# PCM5102a_FG_Small_1.net
KiCad netlist of a schematic drawn in EAGLE
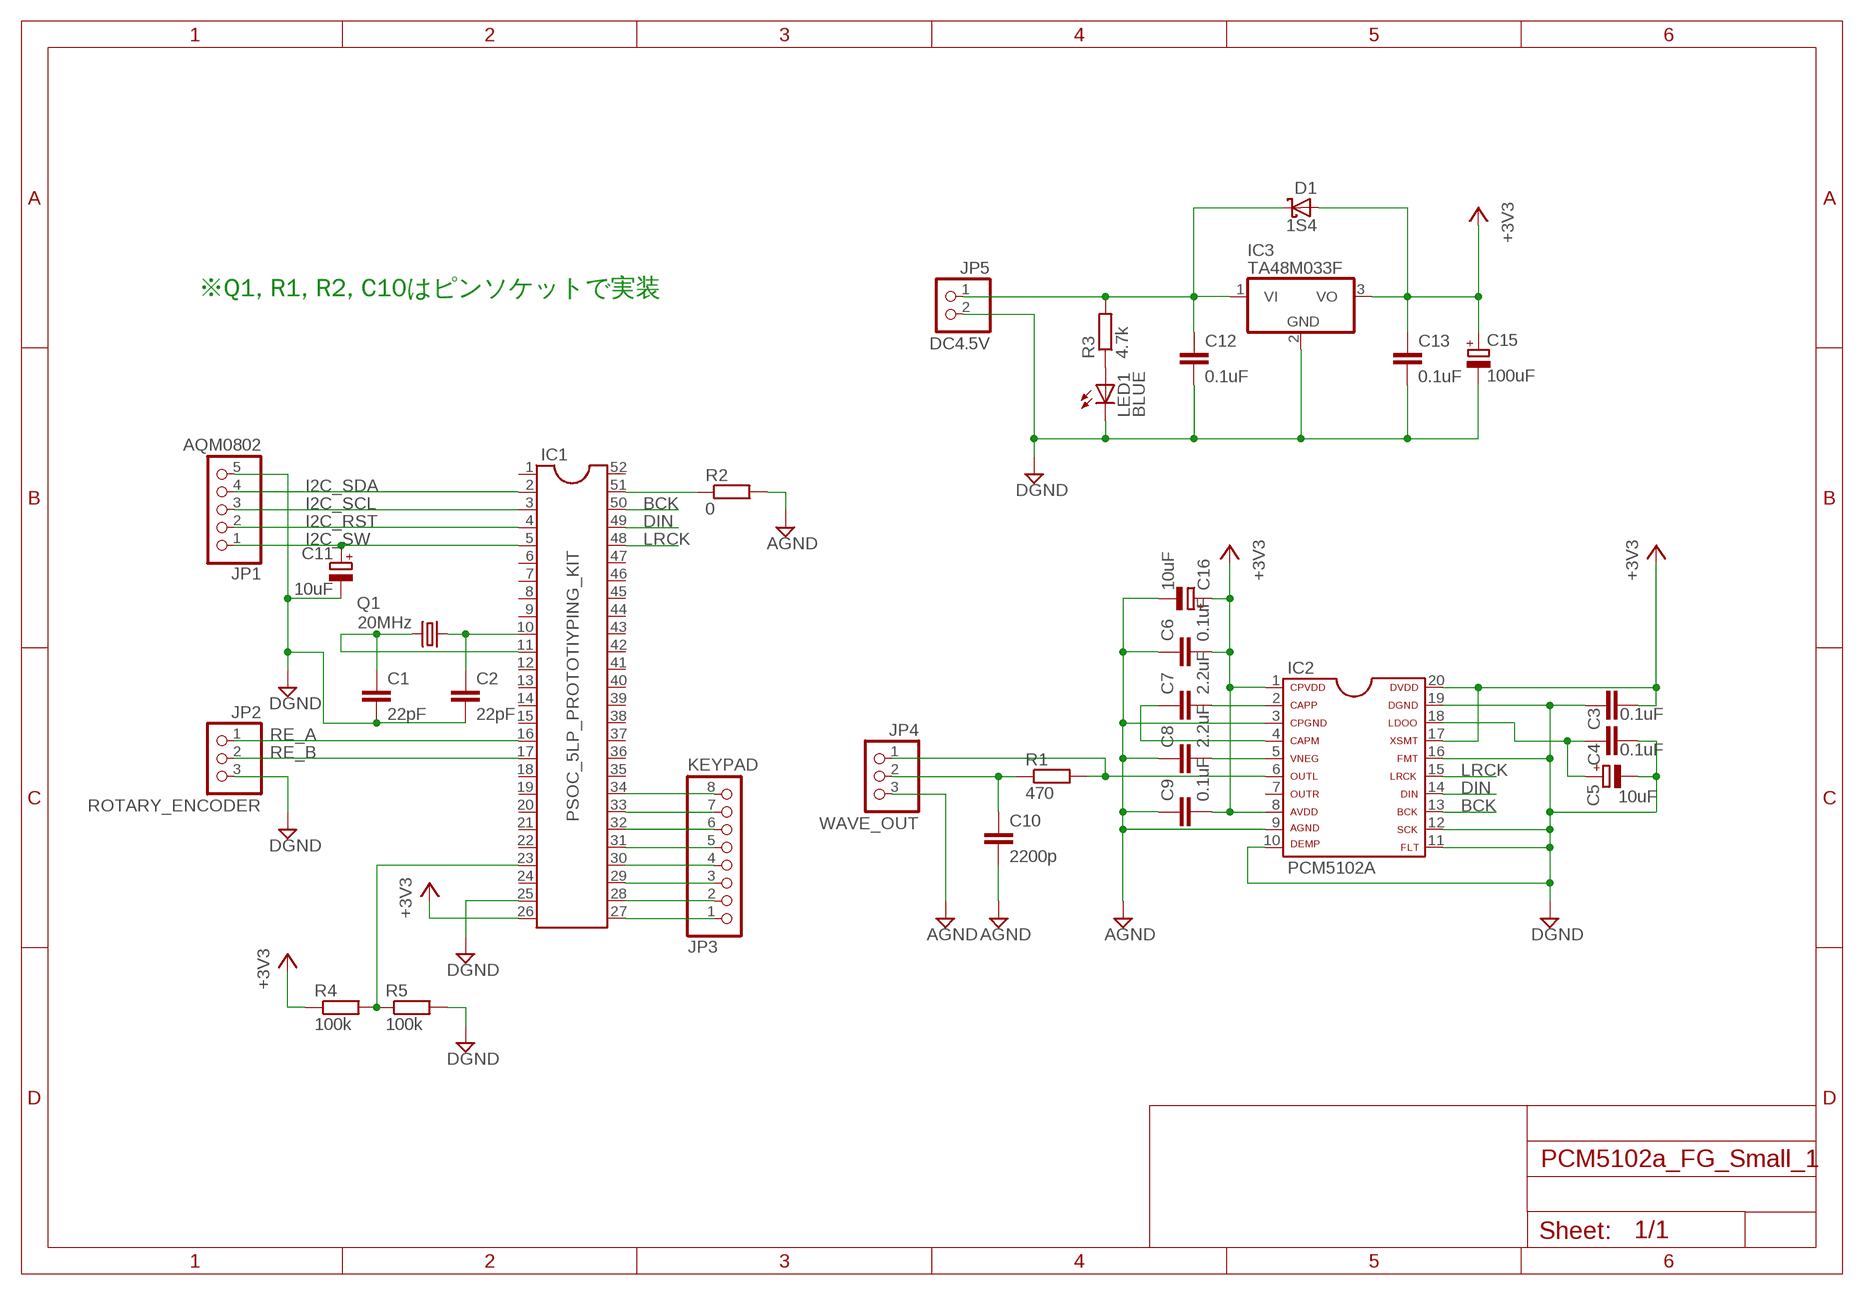
[diagram p0: schematic, sheet 1]

(export (version "E")
  (design (tool "Eeschema 10.0.6"))
  (components
    (comp (ref "C1")
      (value "22pF")
      (footprint "eagle-import:C050-024X044")
      (libsource (lib "eagle-import") (part "C-EU050-024X044"))
    )
    (comp (ref "C2")
      (value "22pF")
      (footprint "eagle-import:C050-024X044")
      (libsource (lib "eagle-import") (part "C-EU050-024X044"))
    )
    (comp (ref "C3")
      (value "0.1uF")
      (footprint "eagle-import:C025-024X044")
      (libsource (lib "eagle-import") (part "C-EU025-024X044"))
    )
    (comp (ref "C4")
      (value "0.1uF")
      (footprint "eagle-import:C025-024X044")
      (libsource (lib "eagle-import") (part "C-EU025-024X044"))
    )
    (comp (ref "C5")
      (value "10uF")
      (footprint "eagle-import:E2,5-5")
      (libsource (lib "eagle-import") (part "CPOL-EUE2.5-5"))
    )
    (comp (ref "C6")
      (value "0.1uF")
      (footprint "eagle-import:C025-024X044")
      (libsource (lib "eagle-import") (part "C-EU025-024X044"))
    )
    (comp (ref "C7")
      (value "2.2uF")
      (footprint "eagle-import:C075-063X106")
      (libsource (lib "eagle-import") (part "C-EU075-063X106"))
    )
    (comp (ref "C8")
      (value "2.2uF")
      (footprint "eagle-import:C075-063X106")
      (libsource (lib "eagle-import") (part "C-EU075-063X106"))
    )
    (comp (ref "C9")
      (value "0.1uF")
      (footprint "eagle-import:C025-024X044")
      (libsource (lib "eagle-import") (part "C-EU025-024X044"))
    )
    (comp (ref "C10")
      (value "2200p")
      (footprint "eagle-import:C050-035X075")
      (libsource (lib "eagle-import") (part "C-EU050-035X075"))
    )
    (comp (ref "C11")
      (value "10uF")
      (footprint "eagle-import:E2,5-5")
      (libsource (lib "eagle-import") (part "CPOL-EUE2.5-5"))
    )
    (comp (ref "C12")
      (value "0.1uF")
      (footprint "eagle-import:C025-024X044")
      (libsource (lib "eagle-import") (part "C-EU025-024X044"))
    )
    (comp (ref "C13")
      (value "0.1uF")
      (footprint "eagle-import:C025-024X044")
      (libsource (lib "eagle-import") (part "C-EU025-024X044"))
    )
    (comp (ref "C15")
      (value "100uF")
      (footprint "eagle-import:E2,5-7")
      (libsource (lib "eagle-import") (part "CPOL-EUE2.5-7"))
    )
    (comp (ref "C16")
      (value "10uF")
      (footprint "eagle-import:E2,5-5")
      (libsource (lib "eagle-import") (part "CPOL-EUE2.5-5"))
    )
    (comp (ref "D1")
      (value "1S4")
      (footprint "eagle-import:DO35-7")
      (libsource (lib "eagle-import") (part "SCHOTTKY-DIODEDO35-7"))
    )
    (comp (ref "IC1")
      (value "PSOC_5LP_PROTOTIYPING_KIT")
      (footprint "eagle-import:DIL52-8")
      (libsource (lib "eagle-import") (part "PSOC_5LP_PROTOTIYPING_KIT"))
    )
    (comp (ref "IC2")
      (value "PCM5102A")
      (footprint "eagle-import:DIL20-6")
      (libsource (lib "eagle-import") (part "PCM5102A"))
    )
    (comp (ref "IC3")
      (value "TA48M033F")
      (footprint "eagle-import:TO220V")
      (libsource (lib "eagle-import") (part "78TV05"))
    )
    (comp (ref "JP1")
      (value "AQM0802")
      (footprint "eagle-import:1X05")
      (libsource (lib "eagle-import") (part "PINHD-1X5"))
    )
    (comp (ref "JP2")
      (value "ROTARY_ENCODER")
      (footprint "eagle-import:1X03")
      (libsource (lib "eagle-import") (part "PINHD-1X3"))
    )
    (comp (ref "JP3")
      (value "KEYPAD")
      (footprint "eagle-import:1X08")
      (libsource (lib "eagle-import") (part "PINHD-1X8"))
    )
    (comp (ref "JP4")
      (value "WAVE_OUT")
      (footprint "eagle-import:1X03")
      (libsource (lib "eagle-import") (part "PINHD-1X3"))
    )
    (comp (ref "JP5")
      (value "DC4.5V")
      (footprint "eagle-import:1X02")
      (libsource (lib "eagle-import") (part "PINHD-1X2"))
    )
    (comp (ref "LED1")
      (value "BLUE")
      (footprint "eagle-import:LED3MM")
      (libsource (lib "eagle-import") (part "LED3MM"))
    )
    (comp (ref "Q1")
      (value "20MHz")
      (footprint "eagle-import:HC49_S")
      (libsource (lib "eagle-import") (part "CRYSTALHC49S"))
    )
    (comp (ref "R1")
      (value "470")
      (footprint "eagle-import:0207_7")
      (libsource (lib "eagle-import") (part "R-EU_0207/7"))
    )
    (comp (ref "R2")
      (value "0")
      (footprint "eagle-import:0207_7")
      (libsource (lib "eagle-import") (part "resistor_R-EU_0207/7"))
    )
    (comp (ref "R3")
      (value "4.7k")
      (footprint "eagle-import:0207_7")
      (libsource (lib "eagle-import") (part "resistor_R-EU_0207/7"))
    )
    (comp (ref "R4")
      (value "100k")
      (footprint "eagle-import:0207_7")
      (libsource (lib "eagle-import") (part "resistor_R-EU_0207/7"))
    )
    (comp (ref "R5")
      (value "100k")
      (footprint "eagle-import:0207_7")
      (libsource (lib "eagle-import") (part "resistor_R-EU_0207/7"))
    )
  )
  (nets
    (net (code "1") (name "+3V3") (class "Default")
      (node (ref "C13") (pin "1") (pinfunction "1_1") (pintype "passive"))
      (node (ref "C15") (pin "+") (pinfunction "+_+") (pintype "passive"))
      (node (ref "C16") (pin "+") (pinfunction "+_+") (pintype "passive"))
      (node (ref "C3") (pin "2") (pinfunction "2_2") (pintype "passive"))
      (node (ref "C6") (pin "2") (pinfunction "2_2") (pintype "passive"))
      (node (ref "C9") (pin "2") (pinfunction "2_2") (pintype "passive"))
      (node (ref "D1") (pin "A") (pinfunction "A_A") (pintype "passive"))
      (node (ref "IC1") (pin "26") (pinfunction "26_26") (pintype "passive"))
      (node (ref "IC2") (pin "1") (pinfunction "1_1") (pintype "passive"))
      (node (ref "IC2") (pin "17") (pinfunction "17_17") (pintype "passive"))
      (node (ref "IC2") (pin "20") (pinfunction "20_20") (pintype "passive"))
      (node (ref "IC2") (pin "8") (pinfunction "8_8") (pintype "passive"))
      (node (ref "IC3") (pin "3") (pinfunction "VO_3") (pintype "passive"))
      (node (ref "R4") (pin "1") (pinfunction "1_1") (pintype "passive"))
    )
    (net (code "2") (name "/BCK") (class "Default")
      (node (ref "IC1") (pin "50") (pinfunction "50_50") (pintype "passive"))
      (node (ref "IC2") (pin "13") (pinfunction "13_13") (pintype "passive"))
    )
    (net (code "3") (name "/DIN") (class "Default")
      (node (ref "IC1") (pin "49") (pinfunction "49_49") (pintype "passive"))
      (node (ref "IC2") (pin "14") (pinfunction "14_14") (pintype "passive"))
    )
    (net (code "4") (name "/I2C_RST") (class "Default")
      (node (ref "IC1") (pin "4") (pinfunction "4_4") (pintype "passive"))
      (node (ref "JP1") (pin "2") (pinfunction "2_2") (pintype "passive"))
    )
    (net (code "5") (name "/I2C_SCL") (class "Default")
      (node (ref "IC1") (pin "3") (pinfunction "3_3") (pintype "passive"))
      (node (ref "JP1") (pin "3") (pinfunction "3_3") (pintype "passive"))
    )
    (net (code "6") (name "/I2C_SDA") (class "Default")
      (node (ref "IC1") (pin "2") (pinfunction "2_2") (pintype "passive"))
      (node (ref "JP1") (pin "4") (pinfunction "4_4") (pintype "passive"))
    )
    (net (code "7") (name "/I2C_SW") (class "Default")
      (node (ref "C11") (pin "+") (pinfunction "+_+") (pintype "passive"))
      (node (ref "IC1") (pin "5") (pinfunction "5_5") (pintype "passive"))
      (node (ref "JP1") (pin "1") (pinfunction "1_1") (pintype "passive"))
    )
    (net (code "8") (name "/LRCK") (class "Default")
      (node (ref "IC1") (pin "48") (pinfunction "48_48") (pintype "passive"))
      (node (ref "IC2") (pin "15") (pinfunction "15_15") (pintype "passive"))
    )
    (net (code "9") (name "/RE_A") (class "Default")
      (node (ref "IC1") (pin "16") (pinfunction "16_16") (pintype "passive"))
      (node (ref "JP2") (pin "1") (pinfunction "1_1") (pintype "passive"))
    )
    (net (code "10") (name "/RE_B") (class "Default")
      (node (ref "IC1") (pin "17") (pinfunction "17_17") (pintype "passive"))
      (node (ref "JP2") (pin "2") (pinfunction "2_2") (pintype "passive"))
    )
    (net (code "11") (name "AGND") (class "Default")
      (node (ref "C10") (pin "2") (pinfunction "2_2") (pintype "passive"))
      (node (ref "C16") (pin "-") (pinfunction "-_-") (pintype "passive"))
      (node (ref "C6") (pin "1") (pinfunction "1_1") (pintype "passive"))
      (node (ref "C8") (pin "1") (pinfunction "1_1") (pintype "passive"))
      (node (ref "C9") (pin "1") (pinfunction "1_1") (pintype "passive"))
      (node (ref "IC2") (pin "3") (pinfunction "3_3") (pintype "passive"))
      (node (ref "IC2") (pin "9") (pinfunction "9_9") (pintype "passive"))
      (node (ref "JP4") (pin "3") (pinfunction "3_3") (pintype "passive"))
      (node (ref "R2") (pin "2") (pinfunction "2_2") (pintype "passive"))
    )
    (net (code "12") (name "DGND") (class "Default")
      (node (ref "C1") (pin "2") (pinfunction "2_2") (pintype "passive"))
      (node (ref "C11") (pin "-") (pinfunction "-_-") (pintype "passive"))
      (node (ref "C12") (pin "2") (pinfunction "2_2") (pintype "passive"))
      (node (ref "C13") (pin "2") (pinfunction "2_2") (pintype "passive"))
      (node (ref "C15") (pin "-") (pinfunction "-_-") (pintype "passive"))
      (node (ref "C2") (pin "2") (pinfunction "2_2") (pintype "passive"))
      (node (ref "C3") (pin "1") (pinfunction "1_1") (pintype "passive"))
      (node (ref "C4") (pin "2") (pinfunction "2_2") (pintype "passive"))
      (node (ref "C5") (pin "-") (pinfunction "-_-") (pintype "passive"))
      (node (ref "IC1") (pin "25") (pinfunction "25_25") (pintype "passive"))
      (node (ref "IC2") (pin "10") (pinfunction "10_10") (pintype "passive"))
      (node (ref "IC2") (pin "11") (pinfunction "11_11") (pintype "passive"))
      (node (ref "IC2") (pin "12") (pinfunction "12_12") (pintype "passive"))
      (node (ref "IC2") (pin "16") (pinfunction "16_16") (pintype "passive"))
      (node (ref "IC2") (pin "19") (pinfunction "19_19") (pintype "passive"))
      (node (ref "IC3") (pin "2") (pinfunction "GND_2") (pintype "passive"))
      (node (ref "JP1") (pin "5") (pinfunction "5_5") (pintype "passive"))
      (node (ref "JP2") (pin "3") (pinfunction "3_3") (pintype "passive"))
      (node (ref "JP5") (pin "2") (pinfunction "2_2") (pintype "passive"))
      (node (ref "LED1") (pin "K") (pinfunction "C_K") (pintype "passive"))
      (node (ref "R5") (pin "2") (pinfunction "2_2") (pintype "passive"))
    )
    (net (code "13") (name "Net-(C1-Pad1)") (class "Default")
      (node (ref "C1") (pin "1") (pinfunction "1_1") (pintype "passive"))
      (node (ref "IC1") (pin "11") (pinfunction "11_11") (pintype "passive"))
      (node (ref "Q1") (pin "2") (pinfunction "2_2") (pintype "passive"))
    )
    (net (code "14") (name "Net-(C2-Pad1)") (class "Default")
      (node (ref "C2") (pin "1") (pinfunction "1_1") (pintype "passive"))
      (node (ref "IC1") (pin "10") (pinfunction "10_10") (pintype "passive"))
      (node (ref "Q1") (pin "1") (pinfunction "1_1") (pintype "passive"))
    )
    (net (code "15") (name "Net-(C4-Pad1)") (class "Default")
      (node (ref "C4") (pin "1") (pinfunction "1_1") (pintype "passive"))
      (node (ref "C5") (pin "+") (pinfunction "+_+") (pintype "passive"))
      (node (ref "IC2") (pin "18") (pinfunction "18_18") (pintype "passive"))
    )
    (net (code "16") (name "Net-(C7-Pad1)") (class "Default")
      (node (ref "C7") (pin "1") (pinfunction "1_1") (pintype "passive"))
      (node (ref "IC2") (pin "4") (pinfunction "4_4") (pintype "passive"))
    )
    (net (code "17") (name "Net-(C7-Pad2)") (class "Default")
      (node (ref "C7") (pin "2") (pinfunction "2_2") (pintype "passive"))
      (node (ref "IC2") (pin "2") (pinfunction "2_2") (pintype "passive"))
    )
    (net (code "18") (name "Net-(C8-Pad2)") (class "Default")
      (node (ref "C8") (pin "2") (pinfunction "2_2") (pintype "passive"))
      (node (ref "IC2") (pin "5") (pinfunction "5_5") (pintype "passive"))
    )
    (net (code "19") (name "Net-(C10-Pad1)") (class "Default")
      (node (ref "C10") (pin "1") (pinfunction "1_1") (pintype "passive"))
      (node (ref "JP4") (pin "2") (pinfunction "2_2") (pintype "passive"))
      (node (ref "R1") (pin "1") (pinfunction "1_1") (pintype "passive"))
    )
    (net (code "20") (name "Net-(IC1-Pad23)") (class "Default")
      (node (ref "IC1") (pin "23") (pinfunction "23_23") (pintype "passive"))
      (node (ref "R4") (pin "2") (pinfunction "2_2") (pintype "passive"))
      (node (ref "R5") (pin "1") (pinfunction "1_1") (pintype "passive"))
    )
    (net (code "21") (name "Net-(IC1-Pad27)") (class "Default")
      (node (ref "IC1") (pin "27") (pinfunction "27_27") (pintype "passive"))
      (node (ref "JP3") (pin "1") (pinfunction "1_1") (pintype "passive"))
    )
    (net (code "22") (name "Net-(IC1-Pad28)") (class "Default")
      (node (ref "IC1") (pin "28") (pinfunction "28_28") (pintype "passive"))
      (node (ref "JP3") (pin "2") (pinfunction "2_2") (pintype "passive"))
    )
    (net (code "23") (name "Net-(IC1-Pad29)") (class "Default")
      (node (ref "IC1") (pin "29") (pinfunction "29_29") (pintype "passive"))
      (node (ref "JP3") (pin "3") (pinfunction "3_3") (pintype "passive"))
    )
    (net (code "24") (name "Net-(IC1-Pad30)") (class "Default")
      (node (ref "IC1") (pin "30") (pinfunction "30_30") (pintype "passive"))
      (node (ref "JP3") (pin "4") (pinfunction "4_4") (pintype "passive"))
    )
    (net (code "25") (name "Net-(IC1-Pad31)") (class "Default")
      (node (ref "IC1") (pin "31") (pinfunction "31_31") (pintype "passive"))
      (node (ref "JP3") (pin "5") (pinfunction "5_5") (pintype "passive"))
    )
    (net (code "26") (name "Net-(IC1-Pad32)") (class "Default")
      (node (ref "IC1") (pin "32") (pinfunction "32_32") (pintype "passive"))
      (node (ref "JP3") (pin "6") (pinfunction "6_6") (pintype "passive"))
    )
    (net (code "27") (name "Net-(IC1-Pad33)") (class "Default")
      (node (ref "IC1") (pin "33") (pinfunction "33_33") (pintype "passive"))
      (node (ref "JP3") (pin "7") (pinfunction "7_7") (pintype "passive"))
    )
    (net (code "28") (name "Net-(IC1-Pad34)") (class "Default")
      (node (ref "IC1") (pin "34") (pinfunction "34_34") (pintype "passive"))
      (node (ref "JP3") (pin "8") (pinfunction "8_8") (pintype "passive"))
    )
    (net (code "29") (name "Net-(IC1-Pad51)") (class "Default")
      (node (ref "IC1") (pin "51") (pinfunction "51_51") (pintype "passive"))
      (node (ref "R2") (pin "1") (pinfunction "1_1") (pintype "passive"))
    )
    (net (code "30") (name "Net-(IC2-Pad6)") (class "Default")
      (node (ref "IC2") (pin "6") (pinfunction "6_6") (pintype "passive"))
      (node (ref "JP4") (pin "1") (pinfunction "1_1") (pintype "passive"))
      (node (ref "R1") (pin "2") (pinfunction "2_2") (pintype "passive"))
    )
    (net (code "31") (name "Net-(IC3-VI)") (class "Default")
      (node (ref "C12") (pin "1") (pinfunction "1_1") (pintype "passive"))
      (node (ref "D1") (pin "C") (pinfunction "C_C") (pintype "passive"))
      (node (ref "IC3") (pin "1") (pinfunction "VI_1") (pintype "input"))
      (node (ref "JP5") (pin "1") (pinfunction "1_1") (pintype "passive"))
      (node (ref "R3") (pin "2") (pinfunction "2_2") (pintype "passive"))
    )
    (net (code "32") (name "Net-(LED1-PadA)") (class "Default")
      (node (ref "LED1") (pin "A") (pinfunction "A_A") (pintype "passive"))
      (node (ref "R3") (pin "1") (pinfunction "1_1") (pintype "passive"))
    )
    (net (code "33") (name "unconnected-(IC1-Pad1)") (class "Default")
      (node (ref "IC1") (pin "1") (pinfunction "1_1") (pintype "passive"))
    )
    (net (code "34") (name "unconnected-(IC1-Pad6)") (class "Default")
      (node (ref "IC1") (pin "6") (pinfunction "6_6") (pintype "passive"))
    )
    (net (code "35") (name "unconnected-(IC1-Pad7)") (class "Default")
      (node (ref "IC1") (pin "7") (pinfunction "7_7") (pintype "passive"))
    )
    (net (code "36") (name "unconnected-(IC1-Pad8)") (class "Default")
      (node (ref "IC1") (pin "8") (pinfunction "8_8") (pintype "passive"))
    )
    (net (code "37") (name "unconnected-(IC1-Pad9)") (class "Default")
      (node (ref "IC1") (pin "9") (pinfunction "9_9") (pintype "passive"))
    )
    (net (code "38") (name "unconnected-(IC1-Pad12)") (class "Default")
      (node (ref "IC1") (pin "12") (pinfunction "12_12") (pintype "passive"))
    )
    (net (code "39") (name "unconnected-(IC1-Pad13)") (class "Default")
      (node (ref "IC1") (pin "13") (pinfunction "13_13") (pintype "passive"))
    )
    (net (code "40") (name "unconnected-(IC1-Pad14)") (class "Default")
      (node (ref "IC1") (pin "14") (pinfunction "14_14") (pintype "passive"))
    )
    (net (code "41") (name "unconnected-(IC1-Pad15)") (class "Default")
      (node (ref "IC1") (pin "15") (pinfunction "15_15") (pintype "passive"))
    )
    (net (code "42") (name "unconnected-(IC1-Pad18)") (class "Default")
      (node (ref "IC1") (pin "18") (pinfunction "18_18") (pintype "passive"))
    )
    (net (code "43") (name "unconnected-(IC1-Pad19)") (class "Default")
      (node (ref "IC1") (pin "19") (pinfunction "19_19") (pintype "passive"))
    )
    (net (code "44") (name "unconnected-(IC1-Pad20)") (class "Default")
      (node (ref "IC1") (pin "20") (pinfunction "20_20") (pintype "passive"))
    )
    (net (code "45") (name "unconnected-(IC1-Pad21)") (class "Default")
      (node (ref "IC1") (pin "21") (pinfunction "21_21") (pintype "passive"))
    )
    (net (code "46") (name "unconnected-(IC1-Pad22)") (class "Default")
      (node (ref "IC1") (pin "22") (pinfunction "22_22") (pintype "passive"))
    )
    (net (code "47") (name "unconnected-(IC1-Pad24)") (class "Default")
      (node (ref "IC1") (pin "24") (pinfunction "24_24") (pintype "passive"))
    )
    (net (code "48") (name "unconnected-(IC1-Pad35)") (class "Default")
      (node (ref "IC1") (pin "35") (pinfunction "35_35") (pintype "passive"))
    )
    (net (code "49") (name "unconnected-(IC1-Pad36)") (class "Default")
      (node (ref "IC1") (pin "36") (pinfunction "36_36") (pintype "passive"))
    )
    (net (code "50") (name "unconnected-(IC1-Pad37)") (class "Default")
      (node (ref "IC1") (pin "37") (pinfunction "37_37") (pintype "passive"))
    )
    (net (code "51") (name "unconnected-(IC1-Pad38)") (class "Default")
      (node (ref "IC1") (pin "38") (pinfunction "38_38") (pintype "passive"))
    )
    (net (code "52") (name "unconnected-(IC1-Pad39)") (class "Default")
      (node (ref "IC1") (pin "39") (pinfunction "39_39") (pintype "passive"))
    )
    (net (code "53") (name "unconnected-(IC1-Pad40)") (class "Default")
      (node (ref "IC1") (pin "40") (pinfunction "40_40") (pintype "passive"))
    )
    (net (code "54") (name "unconnected-(IC1-Pad41)") (class "Default")
      (node (ref "IC1") (pin "41") (pinfunction "41_41") (pintype "passive"))
    )
    (net (code "55") (name "unconnected-(IC1-Pad42)") (class "Default")
      (node (ref "IC1") (pin "42") (pinfunction "42_42") (pintype "passive"))
    )
    (net (code "56") (name "unconnected-(IC1-Pad43)") (class "Default")
      (node (ref "IC1") (pin "43") (pinfunction "43_43") (pintype "passive"))
    )
    (net (code "57") (name "unconnected-(IC1-Pad44)") (class "Default")
      (node (ref "IC1") (pin "44") (pinfunction "44_44") (pintype "passive"))
    )
    (net (code "58") (name "unconnected-(IC1-Pad45)") (class "Default")
      (node (ref "IC1") (pin "45") (pinfunction "45_45") (pintype "passive"))
    )
    (net (code "59") (name "unconnected-(IC1-Pad46)") (class "Default")
      (node (ref "IC1") (pin "46") (pinfunction "46_46") (pintype "passive"))
    )
    (net (code "60") (name "unconnected-(IC1-Pad47)") (class "Default")
      (node (ref "IC1") (pin "47") (pinfunction "47_47") (pintype "passive"))
    )
    (net (code "61") (name "unconnected-(IC1-Pad52)") (class "Default")
      (node (ref "IC1") (pin "52") (pinfunction "52_52") (pintype "passive"))
    )
    (net (code "62") (name "unconnected-(IC2-Pad7)") (class "Default")
      (node (ref "IC2") (pin "7") (pinfunction "7_7") (pintype "passive"))
    )
  )
)
